# SHEET1-.net
KiCad netlist of a schematic drawn in Altium Designer
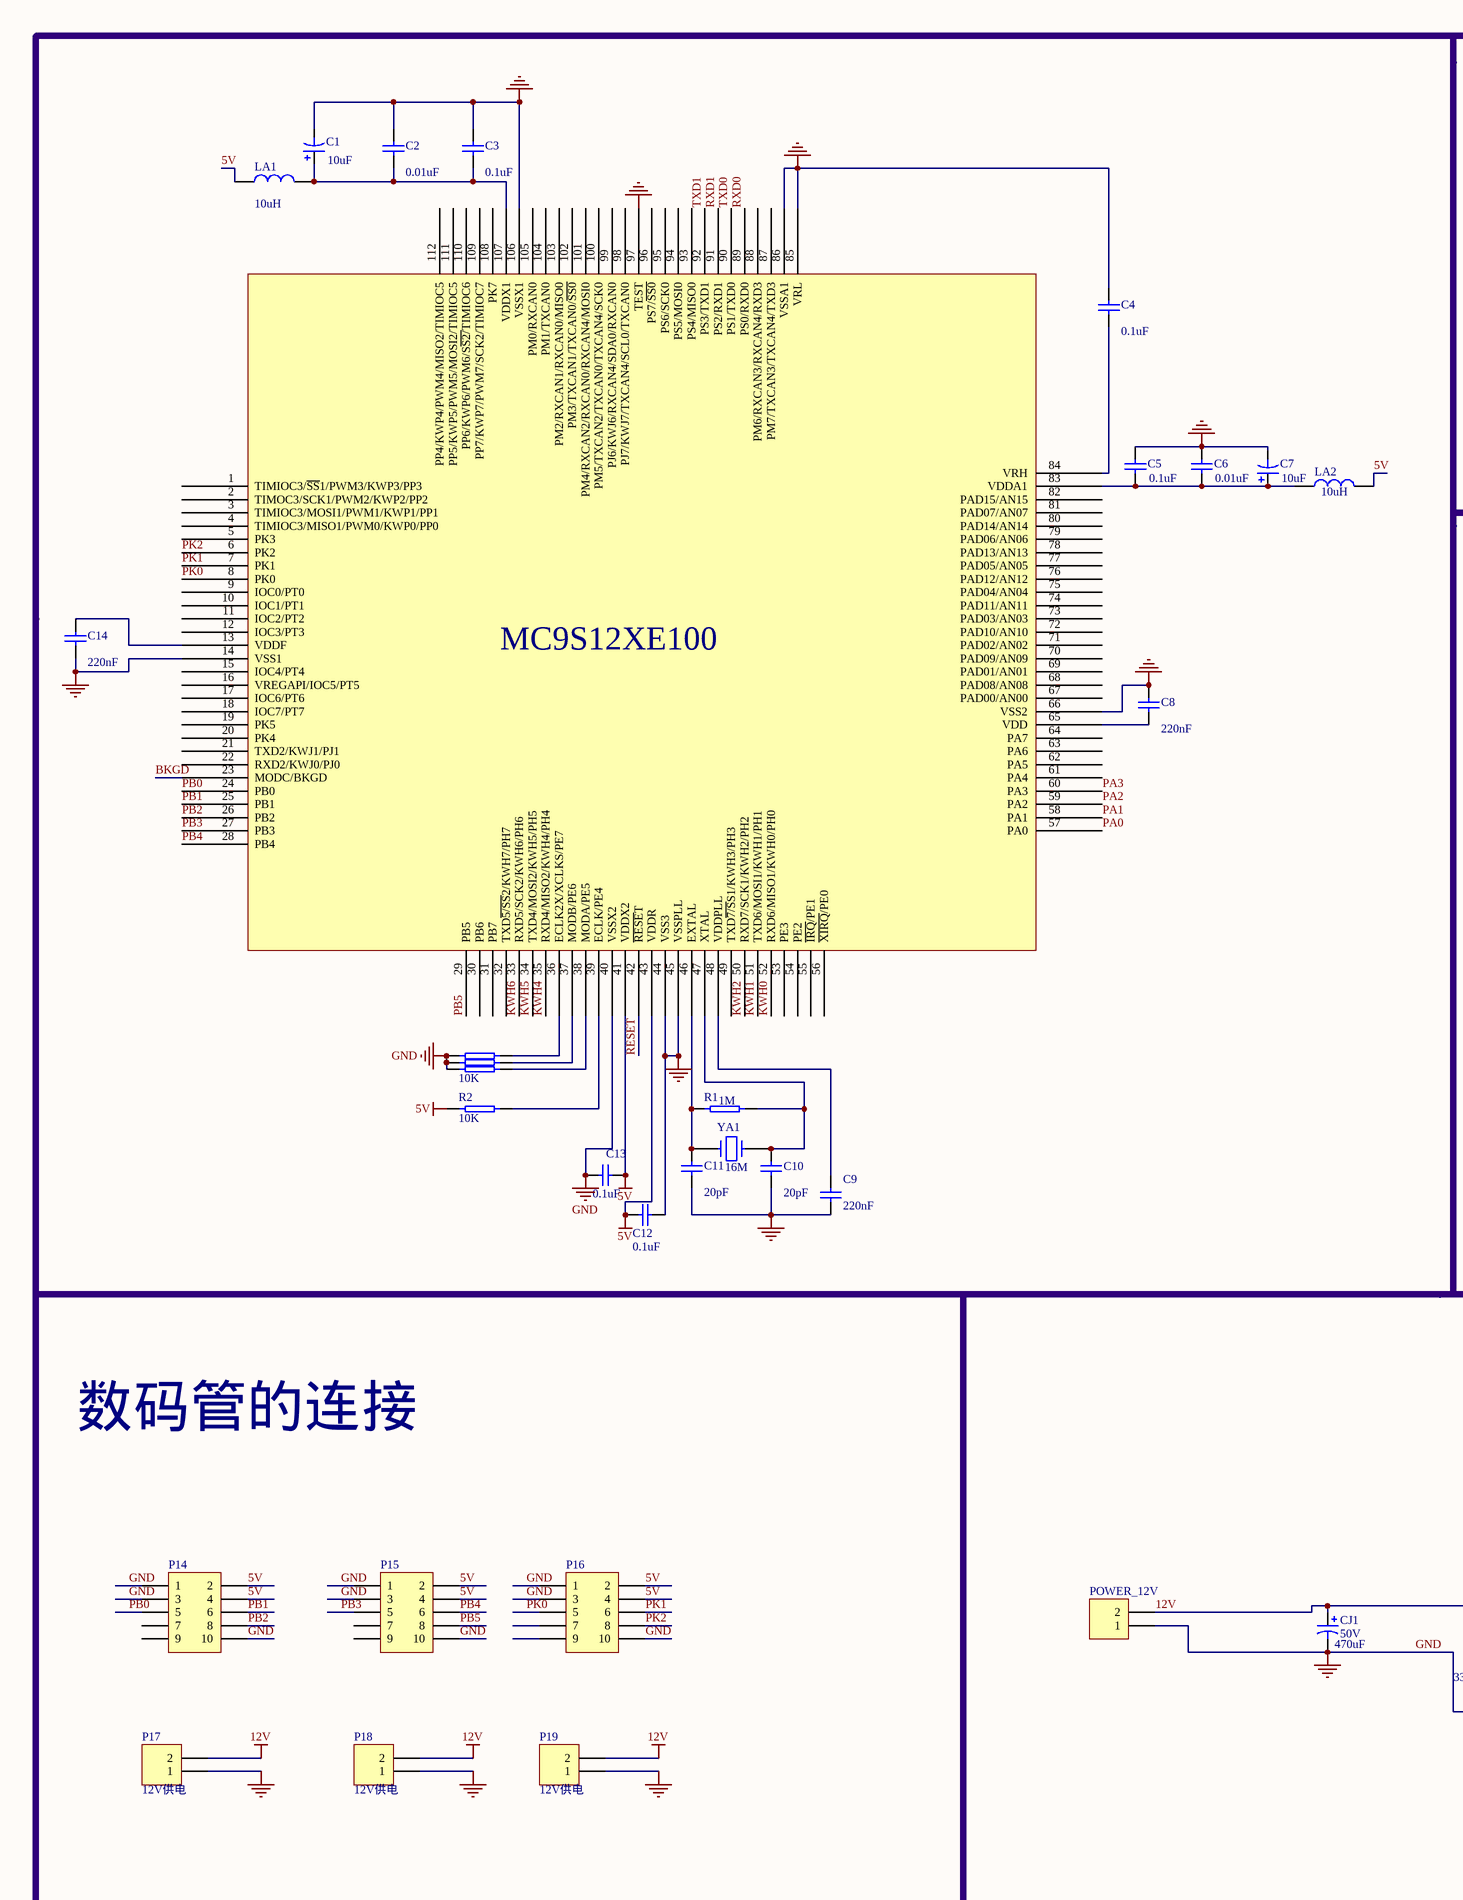
[diagram p0: SHEET1-胡晓.SCHDOC, left]
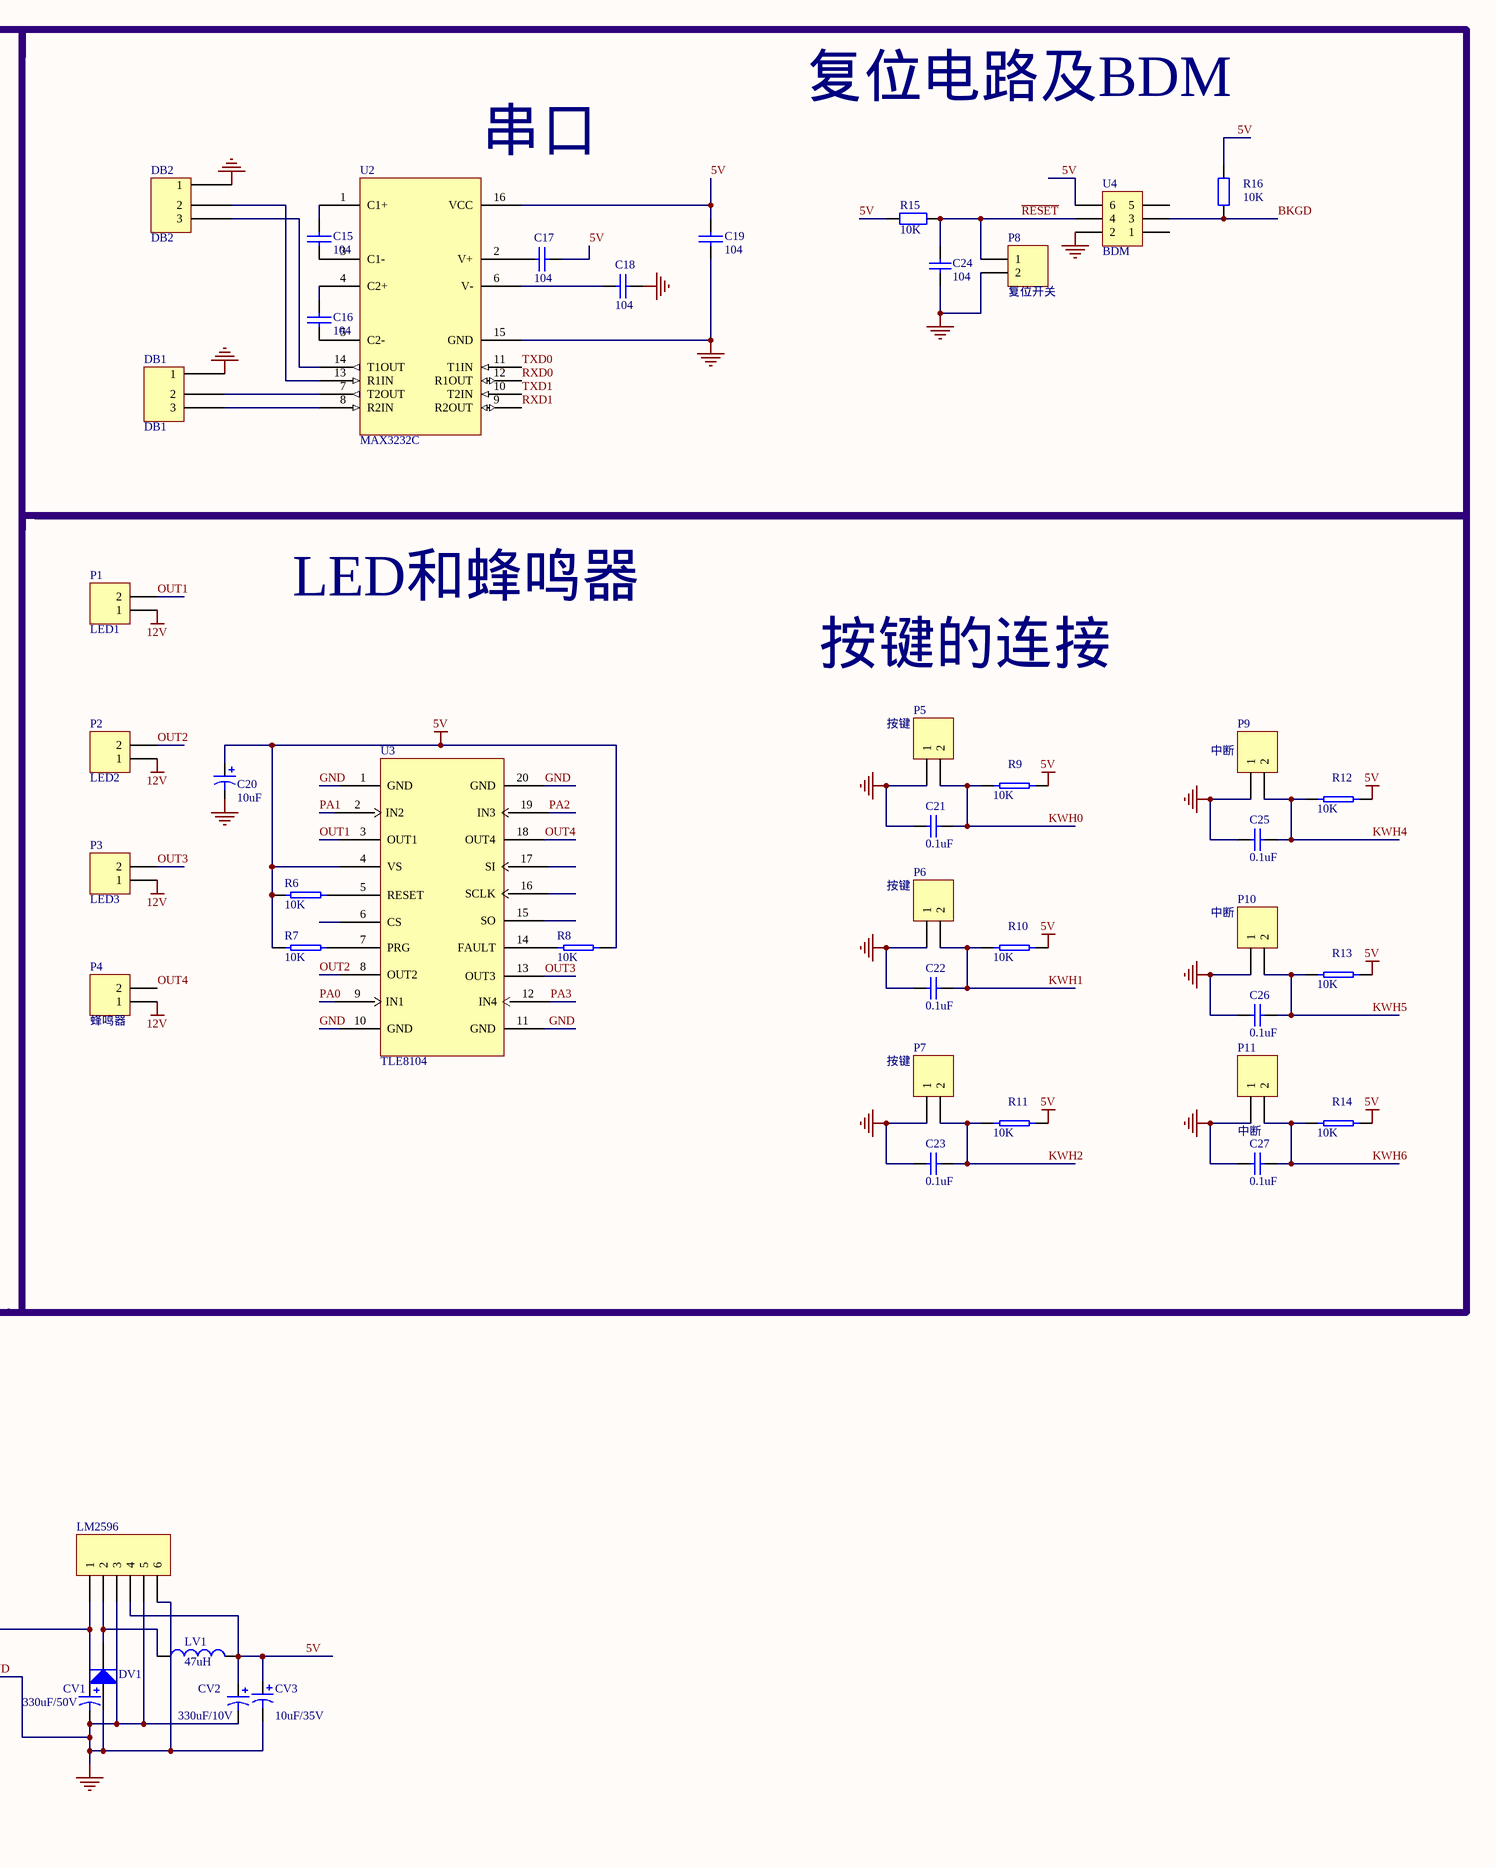
[diagram p1: SHEET1-胡晓.SCHDOC, right]

(export (version "E")
  (design (tool "Eeschema 10.0.6"))
  (components
    (comp (ref "C1")
      (value "CA14")
      (footprint "LC0805-有方向的电容")
      (fields (field (name "ALTIUM_UNNAMED_1") "10uF"))
      (libsource (lib "1") (part "CA14"))
    )
    (comp (ref "C2")
      (value "CA13")
      (footprint "0805")
      (fields (field (name "ALTIUM_UNNAMED_1") "0.01uF"))
      (libsource (lib "1") (part "CA13"))
    )
    (comp (ref "C3")
      (value "CA12")
      (footprint "0805")
      (fields (field (name "ALTIUM_UNNAMED_1") "0.1uF"))
      (libsource (lib "1") (part "CA12"))
    )
    (comp (ref "C4")
      (value "CA11")
      (footprint "0805")
      (fields (field (name "ALTIUM_UNNAMED_1") "0.1uF"))
      (libsource (lib "1") (part "CA11"))
    )
    (comp (ref "C5")
      (value "CA8")
      (footprint "0805")
      (fields (field (name "ALTIUM_UNNAMED_1") "0.1uF"))
      (libsource (lib "1") (part "CA8"))
    )
    (comp (ref "C6")
      (value "CA9")
      (footprint "0805")
      (fields (field (name "ALTIUM_UNNAMED_1") "0.01uF"))
      (libsource (lib "1") (part "CA9"))
    )
    (comp (ref "C7")
      (value "CA10")
      (footprint "LC0805-有方向的电容")
      (fields (field (name "ALTIUM_UNNAMED_1") "10uF"))
      (libsource (lib "1") (part "CA10"))
    )
    (comp (ref "C8")
      (value "CA7")
      (footprint "0805")
      (fields (field (name "ALTIUM_UNNAMED_1") "220nF"))
      (libsource (lib "1") (part "CA7"))
    )
    (comp (ref "C9")
      (value "CA6")
      (footprint "0805")
      (fields (field (name "ALTIUM_UNNAMED_1") "220nF"))
      (libsource (lib "1") (part "CA6"))
    )
    (comp (ref "C10")
      (value "CA5")
      (footprint "0805")
      (fields (field (name "ALTIUM_UNNAMED_1") "20pF"))
      (libsource (lib "1") (part "CA5"))
    )
    (comp (ref "C11")
      (value "CA4")
      (footprint "0805")
      (fields (field (name "ALTIUM_UNNAMED_1") "20pF"))
      (libsource (lib "1") (part "CA4"))
    )
    (comp (ref "C12")
      (value "CA3")
      (footprint "0805")
      (fields (field (name "ALTIUM_UNNAMED_1") "0.1uF"))
      (libsource (lib "1") (part "CA3"))
    )
    (comp (ref "C13")
      (value "CA2")
      (footprint "0805")
      (fields (field (name "ALTIUM_UNNAMED_1") "0.1uF"))
      (libsource (lib "1") (part "CA2"))
    )
    (comp (ref "C14")
      (value "CA1")
      (footprint "0805")
      (fields (field (name "ALTIUM_UNNAMED_1") "220nF"))
      (libsource (lib "1") (part "CA1"))
    )
    (comp (ref "C15")
      (value "104")
      (footprint "0805")
      (description "Capacitor")
      (libsource (lib "FS44B0") (part "CAP_1"))
    )
    (comp (ref "C16")
      (value "104")
      (footprint "0805")
      (description "Capacitor")
      (libsource (lib "FS44B0") (part "CAP_1"))
    )
    (comp (ref "C17")
      (value "104")
      (footprint "0805")
      (description "Capacitor")
      (libsource (lib "FS44B0") (part "CAP_1"))
    )
    (comp (ref "C18")
      (value "104")
      (footprint "0805")
      (description "Capacitor")
      (libsource (lib "FS44B0") (part "CAP_1"))
    )
    (comp (ref "C19")
      (value "104")
      (footprint "0805")
      (description "Capacitor")
      (libsource (lib "FS44B0") (part "CAP_1"))
    )
    (comp (ref "C20")
      (value "C20")
      (footprint "LC0805-有方向的电容")
      (fields (field (name "ALTIUM_UNNAMED_1") "10uF"))
      (libsource (lib "1") (part "CA10"))
    )
    (comp (ref "C21") (value "0.1uF") (footprint "0805") (libsource (lib "1") (part "CA8")))
    (comp (ref "C22") (value "0.1uF") (footprint "0805") (libsource (lib "1") (part "CA8")))
    (comp (ref "C23") (value "0.1uF") (footprint "0805") (libsource (lib "1") (part "CA8")))
    (comp (ref "C24")
      (value "104")
      (footprint "0805")
      (description "Capacitor")
      (fields (field (name "Comment") "Cap"))
      (libsource (lib "FS44B0") (part "Cap"))
    )
    (comp (ref "C25") (value "0.1uF") (footprint "0805") (libsource (lib "1") (part "CA8")))
    (comp (ref "C26") (value "0.1uF") (footprint "0805") (libsource (lib "1") (part "CA8")))
    (comp (ref "C27") (value "0.1uF") (footprint "0805") (libsource (lib "1") (part "CA8")))
    (comp (ref "CJ1")
      (value "50V")
      (footprint "470uF")
      (description "Polarized Capacitor (Radial)")
      (fields (field (name "ALTIUM_VALUE") "470uF"))
      (libsource (lib "Miscellaneous Devices") (part "Cap Pol1"))
    )
    (comp (ref "CV1")
      (value "330uF/50V")
      (footprint "50V/330uF")
      (description "Polarized Capacitor (Radial)")
      (fields (field (name "Comment") "Cap Pol1"))
      (libsource (lib "Miscellaneous Devices") (part "Cap Pol1"))
    )
    (comp (ref "CV2")
      (value "330uF/10V")
      (footprint "10V/330uF")
      (description "Polarized Capacitor (Radial)")
      (fields (field (name "Comment") "Cap Pol1"))
      (libsource (lib "Miscellaneous Devices") (part "Cap Pol1"))
    )
    (comp (ref "CV3")
      (value "10uF/35V")
      (footprint "35V/10uF")
      (description "Polarized Capacitor (Radial)")
      (fields (field (name "Comment") "Cap Pol1"))
      (libsource (lib "Miscellaneous Devices") (part "Cap Pol1"))
    )
    (comp (ref "DB1") (value "DB1") (footprint "kf128-3P") (libsource (lib "1") (part "JA6")))
    (comp (ref "DB2") (value "DB2") (footprint "kf128-3P") (libsource (lib "1") (part "JA6")))
    (comp (ref "DV1")
      (value "Diode")
      (footprint "SMB-二极管")
      (description "Default Diode")
      (libsource (lib "Miscellaneous Devices") (part "Diode"))
    )
    (comp (ref "LA1")
      (value "LA2")
      (footprint "0805")
      (fields (field (name "ALTIUM_UNNAMED_2") "10uH"))
      (libsource (lib "1") (part "LA2"))
    )
    (comp (ref "LA2")
      (value "LA1")
      (footprint "0805")
      (fields (field (name "ALTIUM_UNNAMED_1") "10uH"))
      (libsource (lib "1") (part "LA1"))
    )
    (comp (ref "LM2596")
      (value "LM2596_5")
      (footprint "LM2596")
      (description "Header, 6-Pin")
      (libsource (lib "Miscellaneous Connectors") (part "Header 6"))
    )
    (comp (ref "LV1")
      (value "47uH")
      (footprint "47uH")
      (description "Inductor")
      (libsource (lib "Miscellaneous Devices") (part "Inductor"))
    )
    (comp (ref "MC1") (value "UA1") (footprint "mc9s12xep100") (libsource (lib "1") (part "UA1")))
    (comp (ref "P1")
      (value "LED1")
      (footprint "KF128-2p")
      (description "Header, 2-Pin")
      (libsource (lib "") (part "Header 2_2"))
    )
    (comp (ref "P2")
      (value "LED2")
      (footprint "KF128-2p")
      (description "Header, 2-Pin")
      (libsource (lib "") (part "Header 2_2"))
    )
    (comp (ref "P3")
      (value "LED3")
      (footprint "KF128-2p")
      (description "Header, 2-Pin")
      (libsource (lib "") (part "Header 2_2"))
    )
    (comp (ref "P4")
      (value "蜂鸣器")
      (footprint "KF128-2p")
      (description "Header, 2-Pin")
      (libsource (lib "") (part "Header 2_2"))
    )
    (comp (ref "P5")
      (value "按键")
      (footprint "KF128-2p")
      (description "Header, 2-Pin")
      (libsource (lib "怠速") (part "Header 2"))
    )
    (comp (ref "P6")
      (value "按键")
      (footprint "KF128-2p")
      (description "Header, 2-Pin")
      (libsource (lib "怠速") (part "Header 2"))
    )
    (comp (ref "P7")
      (value "按键")
      (footprint "KF128-2p")
      (description "Header, 2-Pin")
      (libsource (lib "怠速") (part "Header 2"))
    )
    (comp (ref "P8")
      (value "复位开关")
      (footprint "KF128-2p")
      (description "Header, 2-Pin")
      (libsource (lib "") (part "Header 2_1"))
    )
    (comp (ref "P9")
      (value "中断")
      (footprint "KF128-2p")
      (description "Header, 2-Pin")
      (libsource (lib "怠速") (part "Header 2"))
    )
    (comp (ref "P10")
      (value "中断")
      (footprint "KF128-2p")
      (description "Header, 2-Pin")
      (libsource (lib "怠速") (part "Header 2"))
    )
    (comp (ref "P11")
      (value "中断")
      (footprint "KF128-2p")
      (description "Header, 2-Pin")
      (libsource (lib "怠速") (part "Header 2"))
    )
    (comp (ref "P14")
      (value "Header 5X2")
      (footprint "插针5x5")
      (description "Header, 5-Pin, Dual row")
      (libsource (lib "Miscellaneous Connectors") (part "Header 5X2"))
    )
    (comp (ref "P15")
      (value "Header 5X2")
      (footprint "插针5x5")
      (description "Header, 5-Pin, Dual row")
      (libsource (lib "Miscellaneous Connectors") (part "Header 5X2"))
    )
    (comp (ref "P16")
      (value "Header 5X2")
      (footprint "插针5x5")
      (description "Header, 5-Pin, Dual row")
      (libsource (lib "Miscellaneous Connectors") (part "Header 5X2"))
    )
    (comp (ref "P17")
      (value "12V供电")
      (footprint "KF128-2p")
      (description "Header, 2-Pin")
      (libsource (lib "") (part "Header 2_2"))
    )
    (comp (ref "P18")
      (value "12V供电")
      (footprint "KF128-2p")
      (description "Header, 2-Pin")
      (libsource (lib "") (part "Header 2_2"))
    )
    (comp (ref "P19")
      (value "12V供电")
      (footprint "KF128-2p")
      (description "Header, 2-Pin")
      (libsource (lib "") (part "Header 2_2"))
    )
    (comp (ref "POWER_12V")
      (value "Header 2")
      (footprint "KF128-2p")
      (description "Header, 2-Pin")
      (libsource (lib "Miscellaneous Connectors") (part "Header 2"))
    )
    (comp (ref "R1")
      (value "RA8")
      (footprint "0805")
      (fields (field (name "ALTIUM_UNNAMED_1") "1M"))
      (libsource (lib "1") (part "RA8"))
    )
    (comp (ref "R2")
      (value "RA2")
      (footprint "0805")
      (fields (field (name "ALTIUM_UNNAMED_2") "10K"))
      (libsource (lib "1") (part "RA2"))
    )
    (comp (ref "R3")
      (value "RA2")
      (footprint "0805")
      (fields (field (name "ALTIUM_UNNAMED_2") "10K"))
      (libsource (lib "1") (part "RA2"))
    )
    (comp (ref "R4") (value "RA2") (footprint "0805") (libsource (lib "1") (part "RA2")))
    (comp (ref "R5") (value "RA2") (footprint "0805") (libsource (lib "1") (part "RA2")))
    (comp (ref "R6") (value "10K") (footprint "0805") (libsource (lib "1") (part "RA2")))
    (comp (ref "R7") (value "10K") (footprint "0805") (libsource (lib "1") (part "RA2")))
    (comp (ref "R8") (value "10K") (footprint "0805") (libsource (lib "1") (part "RA2")))
    (comp (ref "R9") (value "10K") (footprint "0805") (libsource (lib "1") (part "RA1")))
    (comp (ref "R10") (value "10K") (footprint "0805") (libsource (lib "1") (part "RA1")))
    (comp (ref "R11") (value "10K") (footprint "0805") (libsource (lib "1") (part "RA1")))
    (comp (ref "R12") (value "10K") (footprint "0805") (libsource (lib "1") (part "RA1")))
    (comp (ref "R13") (value "10K") (footprint "0805") (libsource (lib "1") (part "RA1")))
    (comp (ref "R14") (value "10K") (footprint "0805") (libsource (lib "1") (part "RA1")))
    (comp (ref "R15")
      (value "10K")
      (footprint "0805")
      (description "Resistor")
      (fields (field (name "Comment") "Res2"))
      (libsource (lib "FS44B0") (part "Res2"))
    )
    (comp (ref "R16")
      (value "10K")
      (footprint "0805")
      (description "Resistor")
      (fields (field (name "Comment") "Res2"))
      (libsource (lib "") (part "Res2_1"))
    )
    (comp (ref "U2") (value "MAX3232C") (footprint "MAX232") (libsource (lib "FS44B0") (part "max232_1")))
    (comp (ref "U3") (value "TLE8104") (footprint "TEL8104") (libsource (lib "怠速") (part "TLE8104")))
    (comp (ref "U4") (value "BDM") (footprint "BDM") (libsource (lib "1") (part "JA1")))
    (comp (ref "YA1")
      (value "YA1")
      (footprint "XTAL")
      (fields (field (name "ALTIUM_UNNAMED_1") "16M"))
      (libsource (lib "1") (part "YA1"))
    )
  )
  (nets
    (net (code "1") (name "/BKGD") (class "Default")
      (node (ref "MC1") (pin "23") (pinfunction "MODC/BKGD_23") (pintype "passive"))
      (node (ref "R16") (pin "1") (pinfunction "1_1") (pintype "passive"))
      (node (ref "U4") (pin "3") (pinfunction "3_3") (pintype "passive"))
    )
    (net (code "2") (name "/KWH0") (class "Default")
      (node (ref "C21") (pin "2") (pinfunction "2_2") (pintype "passive"))
      (node (ref "MC1") (pin "52") (pinfunction "RXD6/MISO1/KWH0/PH0_52") (pintype "passive"))
      (node (ref "P5") (pin "2") (pinfunction "2_2") (pintype "passive"))
      (node (ref "R9") (pin "1") (pinfunction "1_1") (pintype "passive"))
    )
    (net (code "3") (name "/KWH1") (class "Default")
      (node (ref "C22") (pin "2") (pinfunction "2_2") (pintype "passive"))
      (node (ref "MC1") (pin "51") (pinfunction "TXD6/MOSI1/KWH1/PH1_51") (pintype "passive"))
      (node (ref "P6") (pin "2") (pinfunction "2_2") (pintype "passive"))
      (node (ref "R10") (pin "1") (pinfunction "1_1") (pintype "passive"))
    )
    (net (code "4") (name "/KWH2") (class "Default")
      (node (ref "C23") (pin "2") (pinfunction "2_2") (pintype "passive"))
      (node (ref "MC1") (pin "50") (pinfunction "RXD7/SCK1/KWH2/PH2_50") (pintype "passive"))
      (node (ref "P7") (pin "2") (pinfunction "2_2") (pintype "passive"))
      (node (ref "R11") (pin "1") (pinfunction "1_1") (pintype "passive"))
    )
    (net (code "5") (name "/KWH4") (class "Default")
      (node (ref "C25") (pin "2") (pinfunction "2_2") (pintype "passive"))
      (node (ref "MC1") (pin "35") (pinfunction "RXD4/MISO2/KWH4/PH4_35") (pintype "passive"))
      (node (ref "P9") (pin "2") (pinfunction "2_2") (pintype "passive"))
      (node (ref "R12") (pin "1") (pinfunction "1_1") (pintype "passive"))
    )
    (net (code "6") (name "/KWH5") (class "Default")
      (node (ref "C26") (pin "2") (pinfunction "2_2") (pintype "passive"))
      (node (ref "MC1") (pin "34") (pinfunction "TXD4/MOSI2/KWH5/PH5_34") (pintype "passive"))
      (node (ref "P10") (pin "2") (pinfunction "2_2") (pintype "passive"))
      (node (ref "R13") (pin "1") (pinfunction "1_1") (pintype "passive"))
    )
    (net (code "7") (name "/KWH6") (class "Default")
      (node (ref "C27") (pin "2") (pinfunction "2_2") (pintype "passive"))
      (node (ref "MC1") (pin "33") (pinfunction "RXD5/SCK2/KWH6/PH6_33") (pintype "passive"))
      (node (ref "P11") (pin "2") (pinfunction "2_2") (pintype "passive"))
      (node (ref "R14") (pin "1") (pinfunction "1_1") (pintype "passive"))
    )
    (net (code "8") (name "/OUT1") (class "Default")
      (node (ref "P1") (pin "2") (pinfunction "2_2") (pintype "passive"))
      (node (ref "U3") (pin "3") (pinfunction "OUT1_3") (pintype "passive"))
    )
    (net (code "9") (name "/OUT2") (class "Default")
      (node (ref "P2") (pin "2") (pinfunction "2_2") (pintype "passive"))
      (node (ref "U3") (pin "8") (pinfunction "OUT2_8") (pintype "passive"))
    )
    (net (code "10") (name "/OUT3") (class "Default")
      (node (ref "P3") (pin "2") (pinfunction "2_2") (pintype "passive"))
      (node (ref "U3") (pin "13") (pinfunction "OUT3_13") (pintype "passive"))
    )
    (net (code "11") (name "/OUT4") (class "Default")
      (node (ref "P4") (pin "2") (pinfunction "2_2") (pintype "passive"))
      (node (ref "U3") (pin "18") (pinfunction "OUT4_18") (pintype "passive"))
    )
    (net (code "12") (name "/PA0") (class "Default")
      (node (ref "MC1") (pin "57") (pinfunction "PA0_57") (pintype "passive"))
      (node (ref "U3") (pin "9") (pinfunction "IN1_9") (pintype "passive"))
    )
    (net (code "13") (name "/PA1") (class "Default")
      (node (ref "MC1") (pin "58") (pinfunction "PA1_58") (pintype "passive"))
      (node (ref "U3") (pin "2") (pinfunction "IN2_2") (pintype "passive"))
    )
    (net (code "14") (name "/PA2") (class "Default")
      (node (ref "MC1") (pin "59") (pinfunction "PA2_59") (pintype "passive"))
      (node (ref "U3") (pin "19") (pinfunction "IN3_19") (pintype "passive"))
    )
    (net (code "15") (name "/PA3") (class "Default")
      (node (ref "MC1") (pin "60") (pinfunction "PA3_60") (pintype "passive"))
      (node (ref "U3") (pin "12") (pinfunction "IN4_12") (pintype "passive"))
    )
    (net (code "16") (name "/PB0") (class "Default")
      (node (ref "MC1") (pin "24") (pinfunction "PB0_24") (pintype "passive"))
      (node (ref "P14") (pin "5") (pinfunction "5_5") (pintype "passive"))
    )
    (net (code "17") (name "/PB1") (class "Default")
      (node (ref "MC1") (pin "25") (pinfunction "PB1_25") (pintype "passive"))
      (node (ref "P14") (pin "6") (pinfunction "6_6") (pintype "passive"))
    )
    (net (code "18") (name "/PB2") (class "Default")
      (node (ref "MC1") (pin "26") (pinfunction "PB2_26") (pintype "passive"))
      (node (ref "P14") (pin "8") (pinfunction "8_8") (pintype "passive"))
    )
    (net (code "19") (name "/PB3") (class "Default")
      (node (ref "MC1") (pin "27") (pinfunction "PB3_27") (pintype "passive"))
      (node (ref "P15") (pin "5") (pinfunction "5_5") (pintype "passive"))
    )
    (net (code "20") (name "/PB4") (class "Default")
      (node (ref "MC1") (pin "28") (pinfunction "PB4_28") (pintype "passive"))
      (node (ref "P15") (pin "6") (pinfunction "6_6") (pintype "passive"))
    )
    (net (code "21") (name "/PB5") (class "Default")
      (node (ref "MC1") (pin "29") (pinfunction "PB5_29") (pintype "passive"))
      (node (ref "P15") (pin "8") (pinfunction "8_8") (pintype "passive"))
    )
    (net (code "22") (name "/PK0") (class "Default")
      (node (ref "MC1") (pin "8") (pinfunction "PK0_8") (pintype "passive"))
      (node (ref "P16") (pin "5") (pinfunction "5_5") (pintype "passive"))
    )
    (net (code "23") (name "/PK1") (class "Default")
      (node (ref "MC1") (pin "7") (pinfunction "PK1_7") (pintype "passive"))
      (node (ref "P16") (pin "6") (pinfunction "6_6") (pintype "passive"))
    )
    (net (code "24") (name "/PK2") (class "Default")
      (node (ref "MC1") (pin "6") (pinfunction "PK2_6") (pintype "passive"))
      (node (ref "P16") (pin "8") (pinfunction "8_8") (pintype "passive"))
    )
    (net (code "25") (name "/RESET") (class "Default")
      (node (ref "MC1") (pin "42") (pinfunction "~{RESE}T_42") (pintype "passive"))
    )
    (net (code "26") (name "/RXD0") (class "Default")
      (node (ref "MC1") (pin "89") (pinfunction "PS0/RXD0_89") (pintype "passive"))
      (node (ref "U2") (pin "12") (pinfunction "R1OUT_12") (pintype "bidirectional"))
    )
    (net (code "27") (name "/RXD1") (class "Default")
      (node (ref "MC1") (pin "91") (pinfunction "PS2/RXD1_91") (pintype "passive"))
      (node (ref "U2") (pin "9") (pinfunction "R2OUT_9") (pintype "bidirectional"))
    )
    (net (code "28") (name "/TXD0") (class "Default")
      (node (ref "MC1") (pin "90") (pinfunction "PS1/TXD0_90") (pintype "passive"))
      (node (ref "U2") (pin "11") (pinfunction "T1IN_11") (pintype "input"))
    )
    (net (code "29") (name "/TXD1") (class "Default")
      (node (ref "MC1") (pin "92") (pinfunction "PS3/TXD1_92") (pintype "passive"))
      (node (ref "U2") (pin "10") (pinfunction "T2IN_10") (pintype "input"))
    )
    (net (code "30") (name "/~{RESET}") (class "Default")
      (node (ref "C24") (pin "2") (pinfunction "2_2") (pintype "passive"))
      (node (ref "P8") (pin "1") (pinfunction "1_1") (pintype "passive"))
      (node (ref "R15") (pin "2") (pinfunction "2_2") (pintype "passive"))
      (node (ref "U4") (pin "4") (pinfunction "4_4") (pintype "passive"))
    )
    (net (code "31") (name "5V") (class "Default")
      (node (ref "C12") (pin "2") (pinfunction "2_2") (pintype "passive"))
      (node (ref "C13") (pin "1") (pinfunction "1_1") (pintype "passive"))
      (node (ref "C17") (pin "2") (pinfunction "2_2") (pintype "passive"))
      (node (ref "C19") (pin "1") (pinfunction "1_1") (pintype "passive"))
      (node (ref "C20") (pin "1") (pinfunction "1_1") (pintype "passive"))
      (node (ref "CV2") (pin "1") (pinfunction "1_1") (pintype "passive"))
      (node (ref "CV3") (pin "1") (pinfunction "1_1") (pintype "passive"))
      (node (ref "LA1") (pin "1") (pinfunction "1_1") (pintype "passive"))
      (node (ref "LA2") (pin "2") (pinfunction "2_2") (pintype "passive"))
      (node (ref "LM2596") (pin "4") (pinfunction "4_4") (pintype "passive"))
      (node (ref "LV1") (pin "2") (pinfunction "2_2") (pintype "passive"))
      (node (ref "MC1") (pin "41") (pinfunction "VDDX2_41") (pintype "passive"))
      (node (ref "MC1") (pin "43") (pinfunction "VDDR_43") (pintype "passive"))
      (node (ref "P14") (pin "2") (pinfunction "2_2") (pintype "passive"))
      (node (ref "P14") (pin "4") (pinfunction "4_4") (pintype "passive"))
      (node (ref "P15") (pin "2") (pinfunction "2_2") (pintype "passive"))
      (node (ref "P15") (pin "4") (pinfunction "4_4") (pintype "passive"))
      (node (ref "P16") (pin "2") (pinfunction "2_2") (pintype "passive"))
      (node (ref "P16") (pin "4") (pinfunction "4_4") (pintype "passive"))
      (node (ref "R10") (pin "2") (pinfunction "2_2") (pintype "passive"))
      (node (ref "R11") (pin "2") (pinfunction "2_2") (pintype "passive"))
      (node (ref "R12") (pin "2") (pinfunction "2_2") (pintype "passive"))
      (node (ref "R13") (pin "2") (pinfunction "2_2") (pintype "passive"))
      (node (ref "R14") (pin "2") (pinfunction "2_2") (pintype "passive"))
      (node (ref "R15") (pin "1") (pinfunction "1_1") (pintype "passive"))
      (node (ref "R16") (pin "2") (pinfunction "2_2") (pintype "passive"))
      (node (ref "R2") (pin "2") (pinfunction "2_2") (pintype "passive"))
      (node (ref "R6") (pin "1") (pinfunction "1_1") (pintype "passive"))
      (node (ref "R7") (pin "1") (pinfunction "1_1") (pintype "passive"))
      (node (ref "R8") (pin "2") (pinfunction "2_2") (pintype "passive"))
      (node (ref "R9") (pin "2") (pinfunction "2_2") (pintype "passive"))
      (node (ref "U2") (pin "16") (pinfunction "VCC_16") (pintype "power_in"))
      (node (ref "U3") (pin "4") (pinfunction "VS_4") (pintype "passive"))
      (node (ref "U4") (pin "6") (pinfunction "6_6") (pintype "passive"))
    )
    (net (code "32") (name "12V") (class "Default")
      (node (ref "CJ1") (pin "1") (pinfunction "1_1") (pintype "passive"))
      (node (ref "CV1") (pin "1") (pinfunction "1_1") (pintype "passive"))
      (node (ref "LM2596") (pin "1") (pinfunction "1_1") (pintype "passive"))
      (node (ref "P1") (pin "1") (pinfunction "1_1") (pintype "passive"))
      (node (ref "P17") (pin "2") (pinfunction "2_2") (pintype "passive"))
      (node (ref "P18") (pin "2") (pinfunction "2_2") (pintype "passive"))
      (node (ref "P19") (pin "2") (pinfunction "2_2") (pintype "passive"))
      (node (ref "P2") (pin "1") (pinfunction "1_1") (pintype "passive"))
      (node (ref "P3") (pin "1") (pinfunction "1_1") (pintype "passive"))
      (node (ref "P4") (pin "1") (pinfunction "1_1") (pintype "passive"))
      (node (ref "POWER_12V") (pin "2") (pinfunction "2_2") (pintype "passive"))
    )
    (net (code "33") (name "GND") (class "Default")
      (node (ref "C1") (pin "2") (pinfunction "2_2") (pintype "passive"))
      (node (ref "C10") (pin "1") (pinfunction "1_1") (pintype "passive"))
      (node (ref "C11") (pin "1") (pinfunction "1_1") (pintype "passive"))
      (node (ref "C12") (pin "1") (pinfunction "1_1") (pintype "passive"))
      (node (ref "C13") (pin "2") (pinfunction "2_2") (pintype "passive"))
      (node (ref "C14") (pin "1") (pinfunction "1_1") (pintype "passive"))
      (node (ref "C18") (pin "2") (pinfunction "2_2") (pintype "passive"))
      (node (ref "C19") (pin "2") (pinfunction "2_2") (pintype "passive"))
      (node (ref "C2") (pin "1") (pinfunction "1_1") (pintype "passive"))
      (node (ref "C20") (pin "2") (pinfunction "2_2") (pintype "passive"))
      (node (ref "C21") (pin "1") (pinfunction "1_1") (pintype "passive"))
      (node (ref "C22") (pin "1") (pinfunction "1_1") (pintype "passive"))
      (node (ref "C23") (pin "1") (pinfunction "1_1") (pintype "passive"))
      (node (ref "C24") (pin "1") (pinfunction "1_1") (pintype "passive"))
      (node (ref "C25") (pin "1") (pinfunction "1_1") (pintype "passive"))
      (node (ref "C26") (pin "1") (pinfunction "1_1") (pintype "passive"))
      (node (ref "C27") (pin "1") (pinfunction "1_1") (pintype "passive"))
      (node (ref "C3") (pin "2") (pinfunction "2_2") (pintype "passive"))
      (node (ref "C4") (pin "2") (pinfunction "2_2") (pintype "passive"))
      (node (ref "C5") (pin "2") (pinfunction "2_2") (pintype "passive"))
      (node (ref "C6") (pin "2") (pinfunction "2_2") (pintype "passive"))
      (node (ref "C7") (pin "2") (pinfunction "2_2") (pintype "passive"))
      (node (ref "C8") (pin "1") (pinfunction "1_1") (pintype "passive"))
      (node (ref "C9") (pin "1") (pinfunction "1_1") (pintype "passive"))
      (node (ref "CJ1") (pin "2") (pinfunction "2_2") (pintype "passive"))
      (node (ref "CV1") (pin "2") (pinfunction "2_2") (pintype "passive"))
      (node (ref "CV2") (pin "2") (pinfunction "2_2") (pintype "passive"))
      (node (ref "CV3") (pin "2") (pinfunction "2_2") (pintype "passive"))
      (node (ref "DB1") (pin "1") (pinfunction "1_1") (pintype "passive"))
      (node (ref "DB2") (pin "1") (pinfunction "1_1") (pintype "passive"))
      (node (ref "DV1") (pin "1") (pinfunction "A_1") (pintype "passive"))
      (node (ref "LM2596") (pin "3") (pinfunction "3_3") (pintype "passive"))
      (node (ref "LM2596") (pin "5") (pinfunction "5_5") (pintype "passive"))
      (node (ref "LM2596") (pin "6") (pinfunction "6_6") (pintype "passive"))
      (node (ref "MC1") (pin "106") (pinfunction "VSSX1_106") (pintype "passive"))
      (node (ref "MC1") (pin "14") (pinfunction "VSS1_14") (pintype "passive"))
      (node (ref "MC1") (pin "40") (pinfunction "VSSX2_40") (pintype "passive"))
      (node (ref "MC1") (pin "44") (pinfunction "VSS3_44") (pintype "passive"))
      (node (ref "MC1") (pin "45") (pinfunction "VSSPLL_45") (pintype "passive"))
      (node (ref "MC1") (pin "66") (pinfunction "VSS2_66") (pintype "passive"))
      (node (ref "MC1") (pin "85") (pinfunction "VRL_85") (pintype "passive"))
      (node (ref "MC1") (pin "86") (pinfunction "VSSA1_86") (pintype "passive"))
      (node (ref "MC1") (pin "97") (pinfunction "TEST_97") (pintype "passive"))
      (node (ref "P10") (pin "1") (pinfunction "1_1") (pintype "passive"))
      (node (ref "P11") (pin "1") (pinfunction "1_1") (pintype "passive"))
      (node (ref "P14") (pin "1") (pinfunction "1_1") (pintype "passive"))
      (node (ref "P14") (pin "10") (pinfunction "10_10") (pintype "passive"))
      (node (ref "P14") (pin "3") (pinfunction "3_3") (pintype "passive"))
      (node (ref "P15") (pin "1") (pinfunction "1_1") (pintype "passive"))
      (node (ref "P15") (pin "10") (pinfunction "10_10") (pintype "passive"))
      (node (ref "P15") (pin "3") (pinfunction "3_3") (pintype "passive"))
      (node (ref "P16") (pin "1") (pinfunction "1_1") (pintype "passive"))
      (node (ref "P16") (pin "10") (pinfunction "10_10") (pintype "passive"))
      (node (ref "P16") (pin "3") (pinfunction "3_3") (pintype "passive"))
      (node (ref "P17") (pin "1") (pinfunction "1_1") (pintype "passive"))
      (node (ref "P18") (pin "1") (pinfunction "1_1") (pintype "passive"))
      (node (ref "P19") (pin "1") (pinfunction "1_1") (pintype "passive"))
      (node (ref "P5") (pin "1") (pinfunction "1_1") (pintype "passive"))
      (node (ref "P6") (pin "1") (pinfunction "1_1") (pintype "passive"))
      (node (ref "P7") (pin "1") (pinfunction "1_1") (pintype "passive"))
      (node (ref "P8") (pin "2") (pinfunction "2_2") (pintype "passive"))
      (node (ref "P9") (pin "1") (pinfunction "1_1") (pintype "passive"))
      (node (ref "POWER_12V") (pin "1") (pinfunction "1_1") (pintype "passive"))
      (node (ref "R3") (pin "2") (pinfunction "2_2") (pintype "passive"))
      (node (ref "R4") (pin "2") (pinfunction "2_2") (pintype "passive"))
      (node (ref "R5") (pin "2") (pinfunction "2_2") (pintype "passive"))
      (node (ref "U2") (pin "15") (pinfunction "GND_15") (pintype "power_in"))
      (node (ref "U3") (pin "1") (pinfunction "GND_1") (pintype "passive"))
      (node (ref "U3") (pin "10") (pinfunction "GND_10") (pintype "passive"))
      (node (ref "U3") (pin "11") (pinfunction "GND_11") (pintype "passive"))
      (node (ref "U3") (pin "20") (pinfunction "GND_20") (pintype "passive"))
      (node (ref "U4") (pin "2") (pinfunction "2_2") (pintype "passive"))
    )
    (net (code "34") (name "Net-(DB1-2)") (class "Default")
      (node (ref "DB1") (pin "22") (pinfunction "2_22") (pintype "passive"))
      (node (ref "U2") (pin "7") (pinfunction "T2OUT_7") (pintype "output"))
    )
    (net (code "35") (name "Net-(DB1-3)") (class "Default")
      (node (ref "DB1") (pin "23") (pinfunction "3_23") (pintype "passive"))
      (node (ref "U2") (pin "8") (pinfunction "R2IN_8") (pintype "input"))
    )
    (net (code "36") (name "Net-(DB2-2)") (class "Default")
      (node (ref "DB2") (pin "22") (pinfunction "2_22") (pintype "passive"))
      (node (ref "U2") (pin "13") (pinfunction "R1IN_13") (pintype "input"))
    )
    (net (code "37") (name "Net-(DB2-3)") (class "Default")
      (node (ref "DB2") (pin "23") (pinfunction "3_23") (pintype "passive"))
      (node (ref "U2") (pin "14") (pinfunction "T1OUT_14") (pintype "output"))
    )
    (net (code "38") (name "Net-(DV1-K)") (class "Default")
      (node (ref "DV1") (pin "2") (pinfunction "K_2") (pintype "passive"))
      (node (ref "LM2596") (pin "2") (pinfunction "2_2") (pintype "passive"))
      (node (ref "LV1") (pin "1") (pinfunction "1_1") (pintype "passive"))
    )
    (net (code "39") (name "Net-(MC1-ECLK2X{slash}XCLKS{slash}PE7)") (class "Default")
      (node (ref "MC1") (pin "36") (pinfunction "ECLK2X/XCLKS/PE7_36") (pintype "passive"))
      (node (ref "R5") (pin "1") (pinfunction "1_1") (pintype "passive"))
    )
    (net (code "40") (name "Net-(MC1-ECLK{slash}PE4)") (class "Default")
      (node (ref "MC1") (pin "39") (pinfunction "ECLK/PE4_39") (pintype "passive"))
      (node (ref "R2") (pin "1") (pinfunction "1_1") (pintype "passive"))
    )
    (net (code "41") (name "Net-(MC1-EXTAL)") (class "Default")
      (node (ref "C11") (pin "2") (pinfunction "2_2") (pintype "passive"))
      (node (ref "MC1") (pin "46") (pinfunction "EXTAL_46") (pintype "passive"))
      (node (ref "R1") (pin "1") (pinfunction "1_1") (pintype "passive"))
      (node (ref "YA1") (pin "1") (pinfunction "1_1") (pintype "passive"))
    )
    (net (code "42") (name "Net-(MC1-MODA{slash}PE5)") (class "Default")
      (node (ref "MC1") (pin "38") (pinfunction "MODA/PE5_38") (pintype "passive"))
      (node (ref "R3") (pin "1") (pinfunction "1_1") (pintype "passive"))
    )
    (net (code "43") (name "Net-(MC1-MODB{slash}PE6)") (class "Default")
      (node (ref "MC1") (pin "37") (pinfunction "MODB/PE6_37") (pintype "passive"))
      (node (ref "R4") (pin "1") (pinfunction "1_1") (pintype "passive"))
    )
    (net (code "44") (name "Net-(MC1-VDD)") (class "Default")
      (node (ref "C8") (pin "2") (pinfunction "2_2") (pintype "passive"))
      (node (ref "MC1") (pin "65") (pinfunction "VDD_65") (pintype "passive"))
    )
    (net (code "45") (name "Net-(MC1-VDDA1)") (class "Default")
      (node (ref "C5") (pin "1") (pinfunction "1_1") (pintype "passive"))
      (node (ref "C6") (pin "1") (pinfunction "1_1") (pintype "passive"))
      (node (ref "C7") (pin "1") (pinfunction "1_1") (pintype "passive"))
      (node (ref "LA2") (pin "1") (pinfunction "1_1") (pintype "passive"))
      (node (ref "MC1") (pin "83") (pinfunction "VDDA1_83") (pintype "passive"))
    )
    (net (code "46") (name "Net-(MC1-VDDF)") (class "Default")
      (node (ref "C14") (pin "2") (pinfunction "2_2") (pintype "passive"))
      (node (ref "MC1") (pin "13") (pinfunction "VDDF_13") (pintype "passive"))
    )
    (net (code "47") (name "Net-(MC1-VDDPLL)") (class "Default")
      (node (ref "C9") (pin "2") (pinfunction "2_2") (pintype "passive"))
      (node (ref "MC1") (pin "48") (pinfunction "VDDPLL_48") (pintype "passive"))
    )
    (net (code "48") (name "Net-(MC1-VDDX1)") (class "Default")
      (node (ref "C1") (pin "1") (pinfunction "1_1") (pintype "passive"))
      (node (ref "C2") (pin "2") (pinfunction "2_2") (pintype "passive"))
      (node (ref "C3") (pin "1") (pinfunction "1_1") (pintype "passive"))
      (node (ref "LA1") (pin "2") (pinfunction "2_2") (pintype "passive"))
      (node (ref "MC1") (pin "107") (pinfunction "VDDX1_107") (pintype "passive"))
    )
    (net (code "49") (name "Net-(MC1-VRH)") (class "Default")
      (node (ref "C4") (pin "1") (pinfunction "1_1") (pintype "passive"))
      (node (ref "MC1") (pin "84") (pinfunction "VRH_84") (pintype "passive"))
    )
    (net (code "50") (name "Net-(MC1-XTAL)") (class "Default")
      (node (ref "C10") (pin "2") (pinfunction "2_2") (pintype "passive"))
      (node (ref "MC1") (pin "47") (pinfunction "XTAL_47") (pintype "passive"))
      (node (ref "R1") (pin "2") (pinfunction "2_2") (pintype "passive"))
      (node (ref "YA1") (pin "2") (pinfunction "2_2") (pintype "passive"))
    )
    (net (code "51") (name "Net-(U2-C1+)") (class "Default")
      (node (ref "C15") (pin "1") (pinfunction "1_1") (pintype "passive"))
      (node (ref "U2") (pin "1") (pinfunction "C1+_1") (pintype "passive"))
    )
    (net (code "52") (name "Net-(U2-C1-)") (class "Default")
      (node (ref "C15") (pin "2") (pinfunction "2_2") (pintype "passive"))
      (node (ref "U2") (pin "3") (pinfunction "C1-_3") (pintype "passive"))
    )
    (net (code "53") (name "Net-(U2-C2+)") (class "Default")
      (node (ref "C16") (pin "1") (pinfunction "1_1") (pintype "passive"))
      (node (ref "U2") (pin "4") (pinfunction "C2+_4") (pintype "passive"))
    )
    (net (code "54") (name "Net-(U2-C2-)") (class "Default")
      (node (ref "C16") (pin "2") (pinfunction "2_2") (pintype "passive"))
      (node (ref "U2") (pin "5") (pinfunction "C2-_5") (pintype "passive"))
    )
    (net (code "55") (name "Net-(U2-V+)") (class "Default")
      (node (ref "C17") (pin "1") (pinfunction "1_1") (pintype "passive"))
      (node (ref "U2") (pin "2") (pinfunction "V+_2") (pintype "passive"))
    )
    (net (code "56") (name "Net-(U2-V-)") (class "Default")
      (node (ref "C18") (pin "1") (pinfunction "1_1") (pintype "passive"))
      (node (ref "U2") (pin "6") (pinfunction "V-_6") (pintype "passive"))
    )
    (net (code "57") (name "Net-(U3-FAULT)") (class "Default")
      (node (ref "R8") (pin "1") (pinfunction "1_1") (pintype "passive"))
      (node (ref "U3") (pin "14") (pinfunction "FAULT_14") (pintype "passive"))
    )
    (net (code "58") (name "Net-(U3-PRG)") (class "Default")
      (node (ref "R7") (pin "2") (pinfunction "2_2") (pintype "passive"))
      (node (ref "U3") (pin "7") (pinfunction "PRG_7") (pintype "passive"))
    )
    (net (code "59") (name "Net-(U3-RESET)") (class "Default")
      (node (ref "R6") (pin "2") (pinfunction "2_2") (pintype "passive"))
      (node (ref "U3") (pin "5") (pinfunction "RESET_5") (pintype "passive"))
    )
    (net (code "60") (name "unconnected-(MC1-IOC0{slash}PT0-Pad9)") (class "Default")
      (node (ref "MC1") (pin "9") (pinfunction "IOC0/PT0_9") (pintype "passive"))
    )
    (net (code "61") (name "unconnected-(MC1-IOC1{slash}PT1-Pad10)") (class "Default")
      (node (ref "MC1") (pin "10") (pinfunction "IOC1/PT1_10") (pintype "passive"))
    )
    (net (code "62") (name "unconnected-(MC1-IOC2{slash}PT2-Pad11)") (class "Default")
      (node (ref "MC1") (pin "11") (pinfunction "IOC2/PT2_11") (pintype "passive"))
    )
    (net (code "63") (name "unconnected-(MC1-IOC3{slash}PT3-Pad12)") (class "Default")
      (node (ref "MC1") (pin "12") (pinfunction "IOC3/PT3_12") (pintype "passive"))
    )
    (net (code "64") (name "unconnected-(MC1-IOC4{slash}PT4-Pad15)") (class "Default")
      (node (ref "MC1") (pin "15") (pinfunction "IOC4/PT4_15") (pintype "passive"))
    )
    (net (code "65") (name "unconnected-(MC1-IOC6{slash}PT6-Pad17)") (class "Default")
      (node (ref "MC1") (pin "17") (pinfunction "IOC6/PT6_17") (pintype "passive"))
    )
    (net (code "66") (name "unconnected-(MC1-IOC7{slash}PT7-Pad18)") (class "Default")
      (node (ref "MC1") (pin "18") (pinfunction "IOC7/PT7_18") (pintype "passive"))
    )
    (net (code "67") (name "unconnected-(MC1-PA4-Pad61)") (class "Default")
      (node (ref "MC1") (pin "61") (pinfunction "PA4_61") (pintype "passive"))
    )
    (net (code "68") (name "unconnected-(MC1-PA5-Pad62)") (class "Default")
      (node (ref "MC1") (pin "62") (pinfunction "PA5_62") (pintype "passive"))
    )
    (net (code "69") (name "unconnected-(MC1-PA6-Pad63)") (class "Default")
      (node (ref "MC1") (pin "63") (pinfunction "PA6_63") (pintype "passive"))
    )
    (net (code "70") (name "unconnected-(MC1-PA7-Pad64)") (class "Default")
      (node (ref "MC1") (pin "64") (pinfunction "PA7_64") (pintype "passive"))
    )
    (net (code "71") (name "unconnected-(MC1-PAD00{slash}AN00-Pad67)") (class "Default")
      (node (ref "MC1") (pin "67") (pinfunction "PAD00/AN00_67") (pintype "passive"))
    )
    (net (code "72") (name "unconnected-(MC1-PAD01{slash}AN01-Pad69)") (class "Default")
      (node (ref "MC1") (pin "69") (pinfunction "PAD01/AN01_69") (pintype "passive"))
    )
    (net (code "73") (name "unconnected-(MC1-PAD02{slash}AN02-Pad71)") (class "Default")
      (node (ref "MC1") (pin "71") (pinfunction "PAD02/AN02_71") (pintype "passive"))
    )
    (net (code "74") (name "unconnected-(MC1-PAD03{slash}AN03-Pad73)") (class "Default")
      (node (ref "MC1") (pin "73") (pinfunction "PAD03/AN03_73") (pintype "passive"))
    )
    (net (code "75") (name "unconnected-(MC1-PAD04{slash}AN04-Pad75)") (class "Default")
      (node (ref "MC1") (pin "75") (pinfunction "PAD04/AN04_75") (pintype "passive"))
    )
    (net (code "76") (name "unconnected-(MC1-PAD05{slash}AN05-Pad77)") (class "Default")
      (node (ref "MC1") (pin "77") (pinfunction "PAD05/AN05_77") (pintype "passive"))
    )
    (net (code "77") (name "unconnected-(MC1-PAD06{slash}AN06-Pad79)") (class "Default")
      (node (ref "MC1") (pin "79") (pinfunction "PAD06/AN06_79") (pintype "passive"))
    )
    (net (code "78") (name "unconnected-(MC1-PAD07{slash}AN07-Pad81)") (class "Default")
      (node (ref "MC1") (pin "81") (pinfunction "PAD07/AN07_81") (pintype "passive"))
    )
    (net (code "79") (name "unconnected-(MC1-PAD08{slash}AN08-Pad68)") (class "Default")
      (node (ref "MC1") (pin "68") (pinfunction "PAD08/AN08_68") (pintype "passive"))
    )
    (net (code "80") (name "unconnected-(MC1-PAD09{slash}AN09-Pad70)") (class "Default")
      (node (ref "MC1") (pin "70") (pinfunction "PAD09/AN09_70") (pintype "passive"))
    )
    (net (code "81") (name "unconnected-(MC1-PAD10{slash}AN10-Pad72)") (class "Default")
      (node (ref "MC1") (pin "72") (pinfunction "PAD10/AN10_72") (pintype "passive"))
    )
    (net (code "82") (name "unconnected-(MC1-PAD11{slash}AN11-Pad74)") (class "Default")
      (node (ref "MC1") (pin "74") (pinfunction "PAD11/AN11_74") (pintype "passive"))
    )
    (net (code "83") (name "unconnected-(MC1-PAD12{slash}AN12-Pad76)") (class "Default")
      (node (ref "MC1") (pin "76") (pinfunction "PAD12/AN12_76") (pintype "passive"))
    )
    (net (code "84") (name "unconnected-(MC1-PAD13{slash}AN13-Pad78)") (class "Default")
      (node (ref "MC1") (pin "78") (pinfunction "PAD13/AN13_78") (pintype "passive"))
    )
    (net (code "85") (name "unconnected-(MC1-PAD14{slash}AN14-Pad80)") (class "Default")
      (node (ref "MC1") (pin "80") (pinfunction "PAD14/AN14_80") (pintype "passive"))
    )
    (net (code "86") (name "unconnected-(MC1-PAD15{slash}AN15-Pad82)") (class "Default")
      (node (ref "MC1") (pin "82") (pinfunction "PAD15/AN15_82") (pintype "passive"))
    )
    (net (code "87") (name "unconnected-(MC1-PB6-Pad30)") (class "Default")
      (node (ref "MC1") (pin "30") (pinfunction "PB6_30") (pintype "passive"))
    )
    (net (code "88") (name "unconnected-(MC1-PB7-Pad31)") (class "Default")
      (node (ref "MC1") (pin "31") (pinfunction "PB7_31") (pintype "passive"))
    )
    (net (code "89") (name "unconnected-(MC1-PE2-Pad54)") (class "Default")
      (node (ref "MC1") (pin "54") (pinfunction "PE2_54") (pintype "passive"))
    )
    (net (code "90") (name "unconnected-(MC1-PE3-Pad53)") (class "Default")
      (node (ref "MC1") (pin "53") (pinfunction "PE3_53") (pintype "passive"))
    )
    (net (code "91") (name "unconnected-(MC1-PJ6{slash}KWJ6{slash}RXCAN4{slash}SDA0{slash}RXCAN0-Pad99)") (class "Default")
      (node (ref "MC1") (pin "99") (pinfunction "PJ6/KWJ6/RXCAN4/SDA0/RXCAN0_99") (pintype "passive"))
    )
    (net (code "92") (name "unconnected-(MC1-PJ7{slash}KWJ7{slash}TXCAN4{slash}SCL0{slash}TXCAN0-Pad98)") (class "Default")
      (node (ref "MC1") (pin "98") (pinfunction "PJ7/KWJ7/TXCAN4/SCL0/TXCAN0_98") (pintype "passive"))
    )
    (net (code "93") (name "unconnected-(MC1-PK3-Pad5)") (class "Default")
      (node (ref "MC1") (pin "5") (pinfunction "PK3_5") (pintype "passive"))
    )
    (net (code "94") (name "unconnected-(MC1-PK4-Pad20)") (class "Default")
      (node (ref "MC1") (pin "20") (pinfunction "PK4_20") (pintype "passive"))
    )
    (net (code "95") (name "unconnected-(MC1-PK5-Pad19)") (class "Default")
      (node (ref "MC1") (pin "19") (pinfunction "PK5_19") (pintype "passive"))
    )
    (net (code "96") (name "unconnected-(MC1-PK7-Pad108)") (class "Default")
      (node (ref "MC1") (pin "108") (pinfunction "PK7_108") (pintype "passive"))
    )
    (net (code "97") (name "unconnected-(MC1-PM0{slash}RXCAN0-Pad105)") (class "Default")
      (node (ref "MC1") (pin "105") (pinfunction "PM0/RXCAN0_105") (pintype "passive"))
    )
    (net (code "98") (name "unconnected-(MC1-PM1{slash}TXCAN0-Pad104)") (class "Default")
      (node (ref "MC1") (pin "104") (pinfunction "PM1/TXCAN0_104") (pintype "passive"))
    )
    (net (code "99") (name "unconnected-(MC1-PM2{slash}RXCAN1{slash}RXCAN0{slash}MISO0-Pad103)") (class "Default")
      (node (ref "MC1") (pin "103") (pinfunction "PM2/RXCAN1/RXCAN0/MISO0_103") (pintype "passive"))
    )
    (net (code "100") (name "unconnected-(MC1-PM3{slash}TXCAN1{slash}TXCAN0{slash}~{SS0}-Pad102)") (class "Default")
      (node (ref "MC1") (pin "102") (pinfunction "PM3/TXCAN1/TXCAN0/~{SS0}_102") (pintype "passive"))
    )
    (net (code "101") (name "unconnected-(MC1-PM4{slash}RXCAN2{slash}RXCAN0{slash}RXCAN4{slash}MOSI0-Pad101)") (class "Default")
      (node (ref "MC1") (pin "101") (pinfunction "PM4/RXCAN2/RXCAN0/RXCAN4/MOSI0_101") (pintype "passive"))
    )
    (net (code "102") (name "unconnected-(MC1-PM5{slash}TXCAN2{slash}TXCAN0{slash}TXCAN4{slash}SCK0-Pad100)") (class "Default")
      (node (ref "MC1") (pin "100") (pinfunction "PM5/TXCAN2/TXCAN0/TXCAN4/SCK0_100") (pintype "passive"))
    )
    (net (code "103") (name "unconnected-(MC1-PM6{slash}RXCAN3{slash}RXCAN4{slash}RXD3-Pad88)") (class "Default")
      (node (ref "MC1") (pin "88") (pinfunction "PM6/RXCAN3/RXCAN4/RXD3_88") (pintype "passive"))
    )
    (net (code "104") (name "unconnected-(MC1-PM7{slash}TXCAN3{slash}TXCAN4{slash}TXD3-Pad87)") (class "Default")
      (node (ref "MC1") (pin "87") (pinfunction "PM7/TXCAN3/TXCAN4/TXD3_87") (pintype "passive"))
    )
    (net (code "105") (name "unconnected-(MC1-PP4{slash}KWP4{slash}PWM4{slash}MISO2{slash}TIMIOC5-Pad112)") (class "Default")
      (node (ref "MC1") (pin "112") (pinfunction "PP4/KWP4/PWM4/MISO2/TIMIOC5_112") (pintype "passive"))
    )
    (net (code "106") (name "unconnected-(MC1-PP5{slash}KWP5{slash}PWM5{slash}MOSI2{slash}TIMIOC5-Pad111)") (class "Default")
      (node (ref "MC1") (pin "111") (pinfunction "PP5/KWP5/PWM5/MOSI2/TIMIOC5_111") (pintype "passive"))
    )
    (net (code "107") (name "unconnected-(MC1-PP6{slash}KWP6{slash}PWM6{slash}S~{S2{slash}}TIMIOC6-Pad110)") (class "Default")
      (node (ref "MC1") (pin "110") (pinfunction "PP6/KWP6/PWM6/S~{S2/}TIMIOC6_110") (pintype "passive"))
    )
    (net (code "108") (name "unconnected-(MC1-PP7{slash}KWP7{slash}PWM7{slash}SCK2{slash}TIMIOC7-Pad109)") (class "Default")
      (node (ref "MC1") (pin "109") (pinfunction "PP7/KWP7/PWM7/SCK2/TIMIOC7_109") (pintype "passive"))
    )
    (net (code "109") (name "unconnected-(MC1-PS4{slash}MISO0-Pad93)") (class "Default")
      (node (ref "MC1") (pin "93") (pinfunction "PS4/MISO0_93") (pintype "passive"))
    )
    (net (code "110") (name "unconnected-(MC1-PS5{slash}MOSI0-Pad94)") (class "Default")
      (node (ref "MC1") (pin "94") (pinfunction "PS5/MOSI0_94") (pintype "passive"))
    )
    (net (code "111") (name "unconnected-(MC1-PS6{slash}SCK0-Pad95)") (class "Default")
      (node (ref "MC1") (pin "95") (pinfunction "PS6/SCK0_95") (pintype "passive"))
    )
    (net (code "112") (name "unconnected-(MC1-PS7{slash}~{SS0}-Pad96)") (class "Default")
      (node (ref "MC1") (pin "96") (pinfunction "PS7/~{SS0}_96") (pintype "passive"))
    )
    (net (code "113") (name "unconnected-(MC1-RXD2{slash}KWJ0{slash}PJ0-Pad22)") (class "Default")
      (node (ref "MC1") (pin "22") (pinfunction "RXD2/KWJ0/PJ0_22") (pintype "passive"))
    )
    (net (code "114") (name "unconnected-(MC1-TIMIOC3{slash}MISO1{slash}PWM0{slash}KWP0{slash}PP0-Pad4)") (class "Default")
      (node (ref "MC1") (pin "4") (pinfunction "TIMIOC3/MISO1/PWM0/KWP0/PP0_4") (pintype "passive"))
    )
    (net (code "115") (name "unconnected-(MC1-TIMIOC3{slash}MOSI1{slash}PWM1{slash}KWP1{slash}PP1-Pad3)") (class "Default")
      (node (ref "MC1") (pin "3") (pinfunction "TIMIOC3/MOSI1/PWM1/KWP1/PP1_3") (pintype "passive"))
    )
    (net (code "116") (name "unconnected-(MC1-TIMIOC3{slash}~{SS}1{slash}PWM3{slash}KWP3{slash}PP3-Pad1)") (class "Default")
      (node (ref "MC1") (pin "1") (pinfunction "TIMIOC3/~{SS}1/PWM3/KWP3/PP3_1") (pintype "passive"))
    )
    (net (code "117") (name "unconnected-(MC1-TIMOC3{slash}SCK1{slash}PWM2{slash}KWP2{slash}PP2-Pad2)") (class "Default")
      (node (ref "MC1") (pin "2") (pinfunction "TIMOC3/SCK1/PWM2/KWP2/PP2_2") (pintype "passive"))
    )
    (net (code "118") (name "unconnected-(MC1-TXD2{slash}KWJ1{slash}PJ1-Pad21)") (class "Default")
      (node (ref "MC1") (pin "21") (pinfunction "TXD2/KWJ1/PJ1_21") (pintype "passive"))
    )
    (net (code "119") (name "unconnected-(MC1-TXD~{5{slash}SS}2{slash}KWH7{slash}PH7-Pad32)") (class "Default")
      (node (ref "MC1") (pin "32") (pinfunction "TXD~{5/SS}2/KWH7/PH7_32") (pintype "passive"))
    )
    (net (code "120") (name "unconnected-(MC1-TXD~{7{slash}S}S1{slash}KWH3{slash}PH3-Pad49)") (class "Default")
      (node (ref "MC1") (pin "49") (pinfunction "TXD~{7/S}S1/KWH3/PH3_49") (pintype "passive"))
    )
    (net (code "121") (name "unconnected-(MC1-VREGAPI{slash}IOC5{slash}PT5-Pad16)") (class "Default")
      (node (ref "MC1") (pin "16") (pinfunction "VREGAPI/IOC5/PT5_16") (pintype "passive"))
    )
    (net (code "122") (name "unconnected-(MC1-~{IRQ}{slash}PE1-Pad55)") (class "Default")
      (node (ref "MC1") (pin "55") (pinfunction "~{IRQ}/PE1_55") (pintype "passive"))
    )
    (net (code "123") (name "unconnected-(MC1-~{XIRQ}{slash}PE0-Pad56)") (class "Default")
      (node (ref "MC1") (pin "56") (pinfunction "~{XIRQ}/PE0_56") (pintype "passive"))
    )
    (net (code "124") (name "unconnected-(P14-Pad7)") (class "Default")
      (node (ref "P14") (pin "7") (pinfunction "7_7") (pintype "passive"))
    )
    (net (code "125") (name "unconnected-(P14-Pad9)") (class "Default")
      (node (ref "P14") (pin "9") (pinfunction "9_9") (pintype "passive"))
    )
    (net (code "126") (name "unconnected-(P15-Pad7)") (class "Default")
      (node (ref "P15") (pin "7") (pinfunction "7_7") (pintype "passive"))
    )
    (net (code "127") (name "unconnected-(P15-Pad9)") (class "Default")
      (node (ref "P15") (pin "9") (pinfunction "9_9") (pintype "passive"))
    )
    (net (code "128") (name "unconnected-(P16-Pad7)") (class "Default")
      (node (ref "P16") (pin "7") (pinfunction "7_7") (pintype "passive"))
    )
    (net (code "129") (name "unconnected-(P16-Pad9)") (class "Default")
      (node (ref "P16") (pin "9") (pinfunction "9_9") (pintype "passive"))
    )
    (net (code "130") (name "unconnected-(U3-CS-Pad6)") (class "Default")
      (node (ref "U3") (pin "6") (pinfunction "CS_6") (pintype "passive"))
    )
    (net (code "131") (name "unconnected-(U3-SCLK-Pad16)") (class "Default")
      (node (ref "U3") (pin "16") (pinfunction "SCLK_16") (pintype "passive"))
    )
    (net (code "132") (name "unconnected-(U3-SI-Pad17)") (class "Default")
      (node (ref "U3") (pin "17") (pinfunction "SI_17") (pintype "passive"))
    )
    (net (code "133") (name "unconnected-(U3-SO-Pad15)") (class "Default")
      (node (ref "U3") (pin "15") (pinfunction "SO_15") (pintype "passive"))
    )
    (net (code "134") (name "unconnected-(U4-Pad1)") (class "Default")
      (node (ref "U4") (pin "1") (pinfunction "1_1") (pintype "passive"))
    )
    (net (code "135") (name "unconnected-(U4-Pad5)") (class "Default")
      (node (ref "U4") (pin "5") (pinfunction "5_5") (pintype "passive"))
    )
  )
)
